# Sheet4.net
KiCad netlist of a schematic drawn in Altium Designer
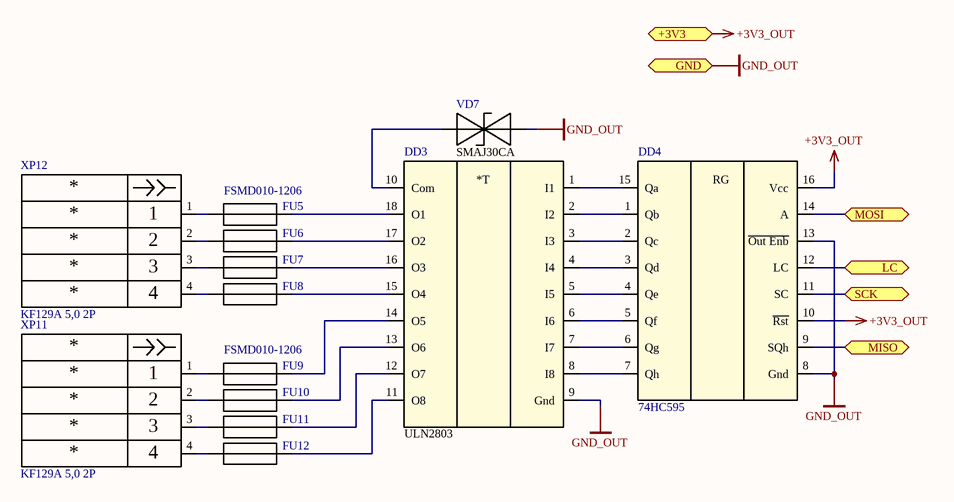
[diagram p0: Sheet4.SchDoc]

(export (version "E")
  (design (tool "Eeschema 10.0.6"))
  (components
    (comp (ref "DD3")
      (value "ULN2803")
      (footprint "SO18 S1.27W9.9")
      (libsource (lib "Россыпь") (part "ULN2803"))
    )
    (comp (ref "DD4")
      (value "74НС595")
      (footprint "SO16 S1.27W6.00")
      (libsource (lib "Россыпь") (part "74НС595"))
    )
    (comp (ref "FU5")
      (value "FSMD010-1206")
      (footprint "Fuse 1206")
      (libsource (lib "Россыпь") (part "FSMDxxx-1206"))
    )
    (comp (ref "FU6")
      (value "FSMDxxx-1206")
      (footprint "Fuse 1206")
      (libsource (lib "Россыпь") (part "FSMDxxx-1206"))
    )
    (comp (ref "FU7")
      (value "FSMDxxx-1206")
      (footprint "Fuse 1206")
      (libsource (lib "Россыпь") (part "FSMDxxx-1206"))
    )
    (comp (ref "FU8")
      (value "FSMDxxx-1206")
      (footprint "Fuse 1206")
      (libsource (lib "Россыпь") (part "FSMDxxx-1206"))
    )
    (comp (ref "FU9")
      (value "FSMD010-1206")
      (footprint "Fuse 1206")
      (libsource (lib "Россыпь") (part "FSMDxxx-1206"))
    )
    (comp (ref "FU10")
      (value "FSMDxxx-1206")
      (footprint "Fuse 1206")
      (libsource (lib "Россыпь") (part "FSMDxxx-1206"))
    )
    (comp (ref "FU11")
      (value "FSMDxxx-1206")
      (footprint "Fuse 1206")
      (libsource (lib "Россыпь") (part "FSMDxxx-1206"))
    )
    (comp (ref "FU12")
      (value "FSMDxxx-1206")
      (footprint "Fuse 1206")
      (libsource (lib "Россыпь") (part "FSMDxxx-1206"))
    )
    (comp (ref "VD7")
      (value "SMAJ30CA")
      (footprint "DO-214AC SMA")
      (libsource (lib "Россыпь") (part "SMAJxxCA"))
    )
    (comp (ref "XP11")
      (value "KF129A 5,0 2P")
      (footprint "KF129A 5,0 2P")
      (fields
        (field (name "NAME1") "*")
        (field (name "NAME2") "*")
        (field (name "NAME3") "*")
        (field (name "NAME") "*")
        (field (name "NAME4") "*")
      )
      (libsource (lib "Россыпь") (part "KF129A 5,0 2P"))
    )
    (comp (ref "XP12")
      (value "KF129A 5,0 2P")
      (footprint "KF129A 5,0 2P")
      (fields
        (field (name "NAME1") "*")
        (field (name "NAME2") "*")
        (field (name "NAME3") "*")
        (field (name "NAME") "*")
        (field (name "NAME4") "*")
      )
      (libsource (lib "Россыпь") (part "KF129A 5,0 2P"))
    )
  )
  (nets
    (net (code "1") (name "+3V3_OUT") (class "Default")
      (node (ref "DD4") (pin "10") (pinfunction "Rst_10") (pintype "passive"))
      (node (ref "DD4") (pin "16") (pinfunction "Vcc_16") (pintype "passive"))
    )
    (net (code "2") (name "/LC") (class "Default")
      (node (ref "DD4") (pin "12") (pinfunction "LC_12") (pintype "passive"))
    )
    (net (code "3") (name "/MISO") (class "Default")
      (node (ref "DD4") (pin "9") (pinfunction "SQh_9") (pintype "passive"))
    )
    (net (code "4") (name "/MOSI") (class "Default")
      (node (ref "DD4") (pin "14") (pinfunction "A_14") (pintype "passive"))
    )
    (net (code "5") (name "/SCK") (class "Default")
      (node (ref "DD4") (pin "11") (pinfunction "SC_11") (pintype "passive"))
    )
    (net (code "6") (name "GND_OUT") (class "Default")
      (node (ref "DD3") (pin "9") (pinfunction "Gnd_9") (pintype "passive"))
      (node (ref "DD4") (pin "13") (pinfunction "Out_Enb_13") (pintype "passive"))
      (node (ref "DD4") (pin "8") (pinfunction "Gnd_8") (pintype "passive"))
      (node (ref "VD7") (pin "1") (pinfunction "1_1") (pintype "passive"))
    )
    (net (code "7") (name "Net-(DD3-Com)") (class "Default")
      (node (ref "DD3") (pin "10") (pinfunction "Com_10") (pintype "passive"))
      (node (ref "VD7") (pin "2") (pinfunction "2_2") (pintype "passive"))
    )
    (net (code "8") (name "Net-(DD3-I1)") (class "Default")
      (node (ref "DD3") (pin "1") (pinfunction "I1_1") (pintype "passive"))
      (node (ref "DD4") (pin "15") (pinfunction "Qa_15") (pintype "passive"))
    )
    (net (code "9") (name "Net-(DD3-I2)") (class "Default")
      (node (ref "DD3") (pin "2") (pinfunction "I2_2") (pintype "passive"))
      (node (ref "DD4") (pin "1") (pinfunction "Qb_1") (pintype "passive"))
    )
    (net (code "10") (name "Net-(DD3-I3)") (class "Default")
      (node (ref "DD3") (pin "3") (pinfunction "I3_3") (pintype "passive"))
      (node (ref "DD4") (pin "2") (pinfunction "Qc_2") (pintype "passive"))
    )
    (net (code "11") (name "Net-(DD3-I4)") (class "Default")
      (node (ref "DD3") (pin "4") (pinfunction "I4_4") (pintype "passive"))
      (node (ref "DD4") (pin "3") (pinfunction "Qd_3") (pintype "passive"))
    )
    (net (code "12") (name "Net-(DD3-I5)") (class "Default")
      (node (ref "DD3") (pin "5") (pinfunction "I5_5") (pintype "passive"))
      (node (ref "DD4") (pin "4") (pinfunction "Qe_4") (pintype "passive"))
    )
    (net (code "13") (name "Net-(DD3-I6)") (class "Default")
      (node (ref "DD3") (pin "6") (pinfunction "I6_6") (pintype "passive"))
      (node (ref "DD4") (pin "5") (pinfunction "Qf_5") (pintype "passive"))
    )
    (net (code "14") (name "Net-(DD3-I7)") (class "Default")
      (node (ref "DD3") (pin "7") (pinfunction "I7_7") (pintype "passive"))
      (node (ref "DD4") (pin "6") (pinfunction "Qg_6") (pintype "passive"))
    )
    (net (code "15") (name "Net-(DD3-I8)") (class "Default")
      (node (ref "DD3") (pin "8") (pinfunction "I8_8") (pintype "passive"))
      (node (ref "DD4") (pin "7") (pinfunction "Qh_7") (pintype "passive"))
    )
    (net (code "16") (name "Net-(DD3-O1)") (class "Default")
      (node (ref "DD3") (pin "18") (pinfunction "O1_18") (pintype "passive"))
      (node (ref "FU5") (pin "2") (pinfunction "2_2") (pintype "passive"))
    )
    (net (code "17") (name "Net-(DD3-O2)") (class "Default")
      (node (ref "DD3") (pin "17") (pinfunction "O2_17") (pintype "passive"))
      (node (ref "FU6") (pin "2") (pinfunction "2_2") (pintype "passive"))
    )
    (net (code "18") (name "Net-(DD3-O3)") (class "Default")
      (node (ref "DD3") (pin "16") (pinfunction "O3_16") (pintype "passive"))
      (node (ref "FU7") (pin "2") (pinfunction "2_2") (pintype "passive"))
    )
    (net (code "19") (name "Net-(DD3-O4)") (class "Default")
      (node (ref "DD3") (pin "15") (pinfunction "O4_15") (pintype "passive"))
      (node (ref "FU8") (pin "2") (pinfunction "2_2") (pintype "passive"))
    )
    (net (code "20") (name "Net-(DD3-O5)") (class "Default")
      (node (ref "DD3") (pin "14") (pinfunction "O5_14") (pintype "passive"))
      (node (ref "FU9") (pin "2") (pinfunction "2_2") (pintype "passive"))
    )
    (net (code "21") (name "Net-(DD3-O6)") (class "Default")
      (node (ref "DD3") (pin "13") (pinfunction "O6_13") (pintype "passive"))
      (node (ref "FU10") (pin "2") (pinfunction "2_2") (pintype "passive"))
    )
    (net (code "22") (name "Net-(DD3-O7)") (class "Default")
      (node (ref "DD3") (pin "12") (pinfunction "O7_12") (pintype "passive"))
      (node (ref "FU11") (pin "2") (pinfunction "2_2") (pintype "passive"))
    )
    (net (code "23") (name "Net-(DD3-O8)") (class "Default")
      (node (ref "DD3") (pin "11") (pinfunction "O8_11") (pintype "passive"))
      (node (ref "FU12") (pin "2") (pinfunction "2_2") (pintype "passive"))
    )
    (net (code "24") (name "Net-(FU5-Pad1)") (class "Default")
      (node (ref "FU5") (pin "1") (pinfunction "1_1") (pintype "passive"))
      (node (ref "XP12") (pin "1") (pinfunction "1_1") (pintype "passive"))
    )
    (net (code "25") (name "Net-(FU6-Pad1)") (class "Default")
      (node (ref "FU6") (pin "1") (pinfunction "1_1") (pintype "passive"))
      (node (ref "XP12") (pin "2") (pinfunction "2_2") (pintype "passive"))
    )
    (net (code "26") (name "Net-(FU7-Pad1)") (class "Default")
      (node (ref "FU7") (pin "1") (pinfunction "1_1") (pintype "passive"))
      (node (ref "XP12") (pin "3") (pinfunction "3_3") (pintype "passive"))
    )
    (net (code "27") (name "Net-(FU8-Pad1)") (class "Default")
      (node (ref "FU8") (pin "1") (pinfunction "1_1") (pintype "passive"))
      (node (ref "XP12") (pin "4") (pinfunction "4_4") (pintype "passive"))
    )
    (net (code "28") (name "Net-(FU9-Pad1)") (class "Default")
      (node (ref "FU9") (pin "1") (pinfunction "1_1") (pintype "passive"))
      (node (ref "XP11") (pin "1") (pinfunction "1_1") (pintype "passive"))
    )
    (net (code "29") (name "Net-(FU10-Pad1)") (class "Default")
      (node (ref "FU10") (pin "1") (pinfunction "1_1") (pintype "passive"))
      (node (ref "XP11") (pin "2") (pinfunction "2_2") (pintype "passive"))
    )
    (net (code "30") (name "Net-(FU11-Pad1)") (class "Default")
      (node (ref "FU11") (pin "1") (pinfunction "1_1") (pintype "passive"))
      (node (ref "XP11") (pin "3") (pinfunction "3_3") (pintype "passive"))
    )
    (net (code "31") (name "Net-(FU12-Pad1)") (class "Default")
      (node (ref "FU12") (pin "1") (pinfunction "1_1") (pintype "passive"))
      (node (ref "XP11") (pin "4") (pinfunction "4_4") (pintype "passive"))
    )
  )
)
